# Support_ESP32-CAM.net
KiCad netlist of a schematic drawn in Altium Designer
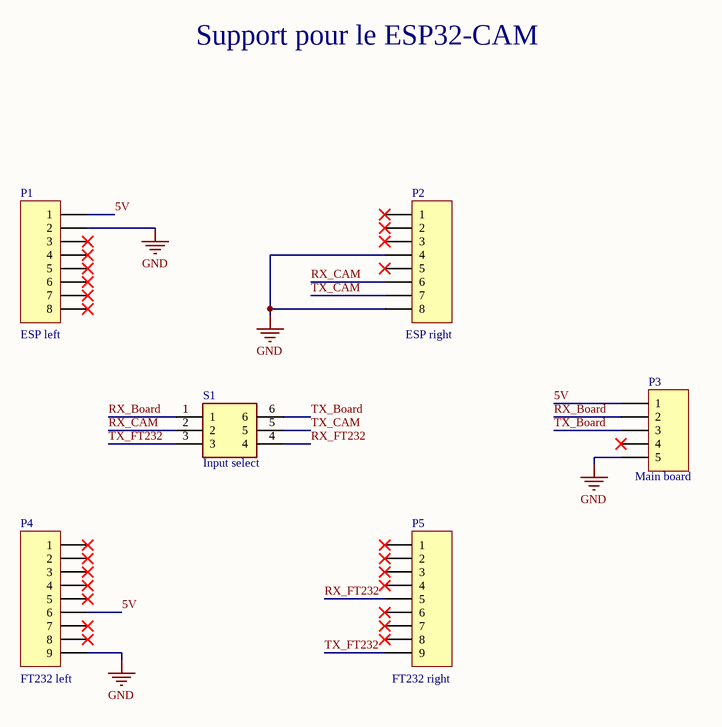
[diagram p0: Support ESP32-CAM.SchDoc]

(export (version "E")
  (design (tool "Eeschema 10.0.6"))
  (components
    (comp (ref "P1")
      (value "Header 8")
      (footprint "HDR1X8")
      (description "Header, 8-Pin")
      (fields (field (name "NAME") "ESP left") (field (name "PUBLISHER") "Altium Limited"))
      (libsource (lib "Miscellaneous Connectors") (part "Header 8"))
    )
    (comp (ref "P2")
      (value "Header 8")
      (footprint "HDR1X8")
      (description "Header, 8-Pin")
      (fields (field (name "NAME") "ESP right") (field (name "PUBLISHER") "Altium Limited"))
      (libsource (lib "") (part "Header 8_1"))
    )
    (comp (ref "P3")
      (value "Header 5")
      (footprint "HDR1X5")
      (description "Header, 5-Pin")
      (fields (field (name "NAME") "Main board") (field (name "PUBLISHER") "Altium Limited"))
      (libsource (lib "Miscellaneous Connectors") (part "Header 5"))
    )
    (comp (ref "P4")
      (value "Header 9")
      (footprint "HDR1X9")
      (description "Header, 9-Pin")
      (fields (field (name "NAME") "FT232 left") (field (name "PUBLISHER") "Altium Limited"))
      (libsource (lib "Miscellaneous Connectors") (part "Header 9"))
    )
    (comp (ref "P5")
      (value "Header 9")
      (footprint "HDR1X9")
      (description "Header, 9-Pin")
      (fields (field (name "NAME") "FT232 right") (field (name "PUBLISHER") "Altium Limited"))
      (libsource (lib "") (part "Header 9_1"))
    )
    (comp (ref "S1")
      (value "MHS222")
      (footprint "DIP320W50P250L860H550Q6N")
      (description "Switch")
      (fields (field (name "NAME") "Input select"))
      (libsource (lib "*") (part "MHS222"))
    )
  )
  (nets
    (net (code "1") (name "/5V") (class "Default")
      (node (ref "P1") (pin "1") (pinfunction "1_1") (pintype "passive"))
      (node (ref "P3") (pin "1") (pinfunction "1_1") (pintype "passive"))
      (node (ref "P4") (pin "6") (pinfunction "6_6") (pintype "passive"))
    )
    (net (code "2") (name "/RX_Board") (class "Default")
      (node (ref "P3") (pin "2") (pinfunction "2_2") (pintype "passive"))
      (node (ref "S1") (pin "1") (pinfunction "1_1") (pintype "passive"))
    )
    (net (code "3") (name "/RX_CAM") (class "Default")
      (node (ref "P2") (pin "6") (pinfunction "6_6") (pintype "passive"))
      (node (ref "S1") (pin "2") (pinfunction "2_2") (pintype "passive"))
    )
    (net (code "4") (name "/RX_FT232") (class "Default")
      (node (ref "P5") (pin "5") (pinfunction "5_5") (pintype "passive"))
      (node (ref "S1") (pin "4") (pinfunction "4_4") (pintype "passive"))
    )
    (net (code "5") (name "/TX_Board") (class "Default")
      (node (ref "P3") (pin "3") (pinfunction "3_3") (pintype "passive"))
      (node (ref "S1") (pin "6") (pinfunction "6_6") (pintype "passive"))
    )
    (net (code "6") (name "/TX_CAM") (class "Default")
      (node (ref "P2") (pin "7") (pinfunction "7_7") (pintype "passive"))
      (node (ref "S1") (pin "5") (pinfunction "5_5") (pintype "passive"))
    )
    (net (code "7") (name "/TX_FT232") (class "Default")
      (node (ref "P5") (pin "9") (pinfunction "9_9") (pintype "passive"))
      (node (ref "S1") (pin "3") (pinfunction "3_3") (pintype "passive"))
    )
    (net (code "8") (name "GND") (class "Default")
      (node (ref "P1") (pin "2") (pinfunction "2_2") (pintype "passive"))
      (node (ref "P2") (pin "4") (pinfunction "4_4") (pintype "passive"))
      (node (ref "P2") (pin "8") (pinfunction "8_8") (pintype "passive"))
      (node (ref "P3") (pin "5") (pinfunction "5_5") (pintype "passive"))
      (node (ref "P4") (pin "9") (pinfunction "9_9") (pintype "passive"))
    )
    (net (code "9") (name "unconnected-(P1-Pad3)") (class "Default")
      (node (ref "P1") (pin "3") (pinfunction "3_3") (pintype "passive+no_connect"))
    )
    (net (code "10") (name "unconnected-(P1-Pad4)") (class "Default")
      (node (ref "P1") (pin "4") (pinfunction "4_4") (pintype "passive+no_connect"))
    )
    (net (code "11") (name "unconnected-(P1-Pad5)") (class "Default")
      (node (ref "P1") (pin "5") (pinfunction "5_5") (pintype "passive+no_connect"))
    )
    (net (code "12") (name "unconnected-(P1-Pad6)") (class "Default")
      (node (ref "P1") (pin "6") (pinfunction "6_6") (pintype "passive+no_connect"))
    )
    (net (code "13") (name "unconnected-(P1-Pad7)") (class "Default")
      (node (ref "P1") (pin "7") (pinfunction "7_7") (pintype "passive+no_connect"))
    )
    (net (code "14") (name "unconnected-(P1-Pad8)") (class "Default")
      (node (ref "P1") (pin "8") (pinfunction "8_8") (pintype "passive+no_connect"))
    )
    (net (code "15") (name "unconnected-(P2-Pad1)") (class "Default")
      (node (ref "P2") (pin "1") (pinfunction "1_1") (pintype "passive+no_connect"))
    )
    (net (code "16") (name "unconnected-(P2-Pad2)") (class "Default")
      (node (ref "P2") (pin "2") (pinfunction "2_2") (pintype "passive+no_connect"))
    )
    (net (code "17") (name "unconnected-(P2-Pad3)") (class "Default")
      (node (ref "P2") (pin "3") (pinfunction "3_3") (pintype "passive+no_connect"))
    )
    (net (code "18") (name "unconnected-(P2-Pad5)") (class "Default")
      (node (ref "P2") (pin "5") (pinfunction "5_5") (pintype "passive+no_connect"))
    )
    (net (code "19") (name "unconnected-(P3-Pad4)") (class "Default")
      (node (ref "P3") (pin "4") (pinfunction "4_4") (pintype "passive+no_connect"))
    )
    (net (code "20") (name "unconnected-(P4-Pad1)") (class "Default")
      (node (ref "P4") (pin "1") (pinfunction "1_1") (pintype "passive+no_connect"))
    )
    (net (code "21") (name "unconnected-(P4-Pad2)") (class "Default")
      (node (ref "P4") (pin "2") (pinfunction "2_2") (pintype "passive+no_connect"))
    )
    (net (code "22") (name "unconnected-(P4-Pad3)") (class "Default")
      (node (ref "P4") (pin "3") (pinfunction "3_3") (pintype "passive+no_connect"))
    )
    (net (code "23") (name "unconnected-(P4-Pad4)") (class "Default")
      (node (ref "P4") (pin "4") (pinfunction "4_4") (pintype "passive+no_connect"))
    )
    (net (code "24") (name "unconnected-(P4-Pad5)") (class "Default")
      (node (ref "P4") (pin "5") (pinfunction "5_5") (pintype "passive+no_connect"))
    )
    (net (code "25") (name "unconnected-(P4-Pad7)") (class "Default")
      (node (ref "P4") (pin "7") (pinfunction "7_7") (pintype "passive+no_connect"))
    )
    (net (code "26") (name "unconnected-(P4-Pad8)") (class "Default")
      (node (ref "P4") (pin "8") (pinfunction "8_8") (pintype "passive+no_connect"))
    )
    (net (code "27") (name "unconnected-(P5-Pad1)") (class "Default")
      (node (ref "P5") (pin "1") (pinfunction "1_1") (pintype "passive+no_connect"))
    )
    (net (code "28") (name "unconnected-(P5-Pad2)") (class "Default")
      (node (ref "P5") (pin "2") (pinfunction "2_2") (pintype "passive+no_connect"))
    )
    (net (code "29") (name "unconnected-(P5-Pad3)") (class "Default")
      (node (ref "P5") (pin "3") (pinfunction "3_3") (pintype "passive+no_connect"))
    )
    (net (code "30") (name "unconnected-(P5-Pad4)") (class "Default")
      (node (ref "P5") (pin "4") (pinfunction "4_4") (pintype "passive+no_connect"))
    )
    (net (code "31") (name "unconnected-(P5-Pad6)") (class "Default")
      (node (ref "P5") (pin "6") (pinfunction "6_6") (pintype "passive+no_connect"))
    )
    (net (code "32") (name "unconnected-(P5-Pad7)") (class "Default")
      (node (ref "P5") (pin "7") (pinfunction "7_7") (pintype "passive+no_connect"))
    )
    (net (code "33") (name "unconnected-(P5-Pad8)") (class "Default")
      (node (ref "P5") (pin "8") (pinfunction "8_8") (pintype "passive+no_connect"))
    )
  )
)
